# BackEMF.net
KiCad netlist of a schematic drawn in Altium Designer
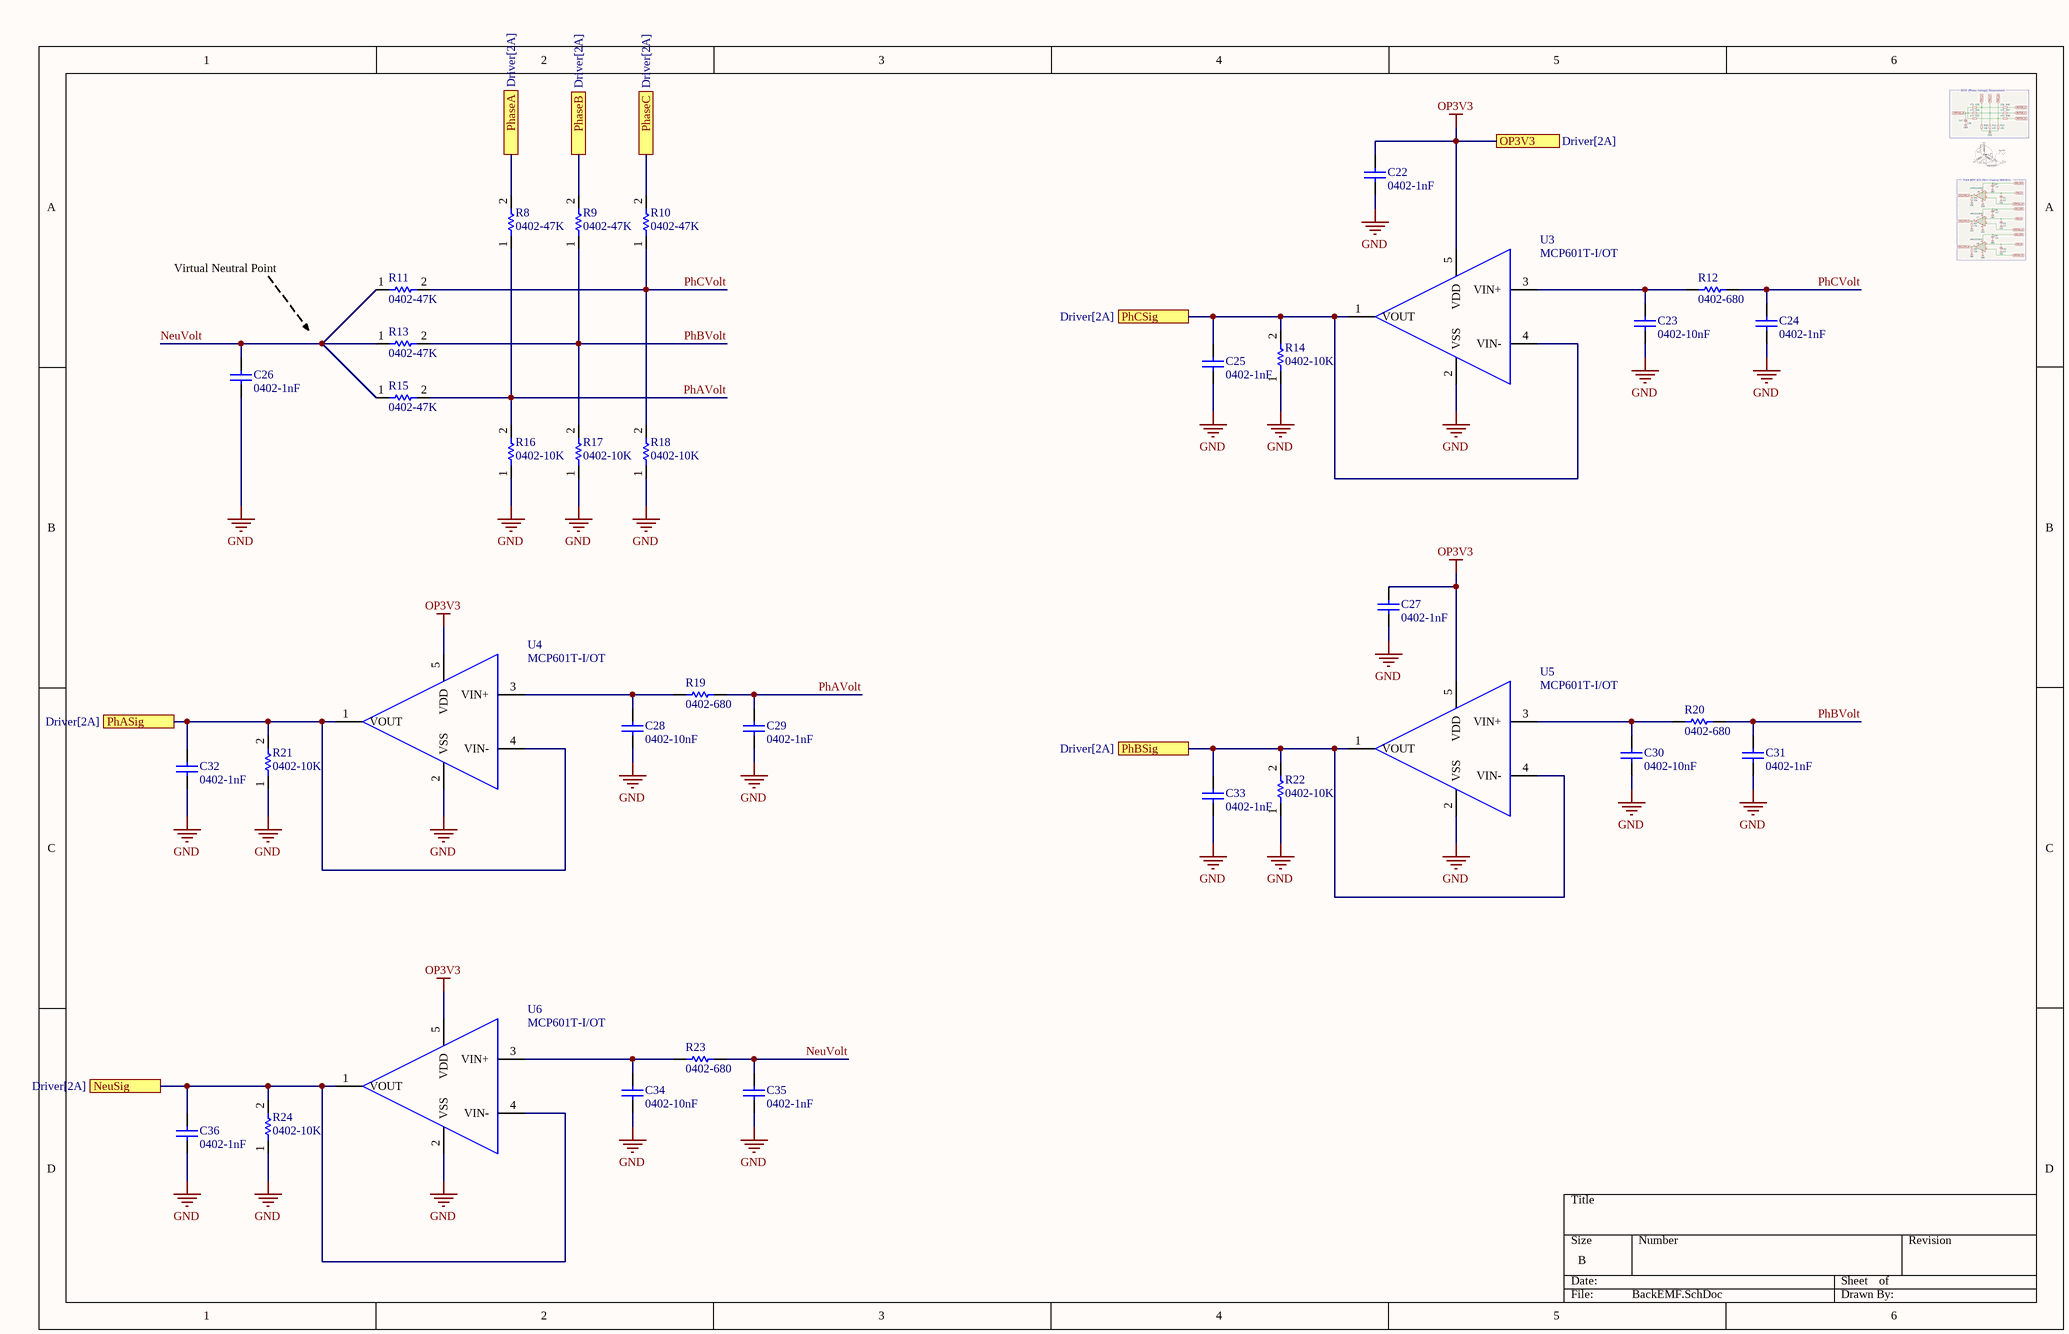
[diagram p0: BackEMF.SchDoc]

(export (version "E")
  (design (tool "Eeschema 10.0.6"))
  (components
    (comp (ref "C22")
      (value "0402-1nF")
      (footprint "CAPC0402(1005)60_N")
      (description "Capacitor 1nF 0402")
      (fields (field (name "TOLERANCE") "20%"))
      (libsource (lib "") (part "0402_1"))
    )
    (comp (ref "C23")
      (value "0402-10nF")
      (footprint "CAPC0402(1005)60_N")
      (description "Capacitor 10nF 0402")
      (fields (field (name "TOLERANCE") "20%"))
      (libsource (lib "") (part "0402_1"))
    )
    (comp (ref "C24")
      (value "0402-1nF")
      (footprint "CAPC0402(1005)60_N")
      (description "Capacitor 1nF 0402")
      (fields (field (name "TOLERANCE") "20%"))
      (libsource (lib "") (part "0402_1"))
    )
    (comp (ref "C25")
      (value "0402-1nF")
      (footprint "CAPC0402(1005)60_N")
      (description "Capacitor 1nF 0402")
      (fields (field (name "TOLERANCE") "20%"))
      (libsource (lib "") (part "0402_1"))
    )
    (comp (ref "C26")
      (value "0402-1nF")
      (footprint "CAPC0402(1005)60_N")
      (description "Capacitor 1nF 0402")
      (fields (field (name "TOLERANCE") "20%"))
      (libsource (lib "") (part "0402_1"))
    )
    (comp (ref "C27")
      (value "0402-1nF")
      (footprint "CAPC0402(1005)60_N")
      (description "Capacitor 1nF 0402")
      (fields (field (name "TOLERANCE") "20%"))
      (libsource (lib "") (part "0402_1"))
    )
    (comp (ref "C28")
      (value "0402-10nF")
      (footprint "CAPC0402(1005)60_N")
      (description "Capacitor 10nF 0402")
      (fields (field (name "TOLERANCE") "20%"))
      (libsource (lib "") (part "0402_1"))
    )
    (comp (ref "C29")
      (value "0402-1nF")
      (footprint "CAPC0402(1005)60_N")
      (description "Capacitor 1nF 0402")
      (fields (field (name "TOLERANCE") "20%"))
      (libsource (lib "") (part "0402_1"))
    )
    (comp (ref "C30")
      (value "0402-10nF")
      (footprint "CAPC0402(1005)60_N")
      (description "Capacitor 10nF 0402")
      (fields (field (name "TOLERANCE") "20%"))
      (libsource (lib "") (part "0402_1"))
    )
    (comp (ref "C31")
      (value "0402-1nF")
      (footprint "CAPC0402(1005)60_N")
      (description "Capacitor 1nF 0402")
      (fields (field (name "TOLERANCE") "20%"))
      (libsource (lib "") (part "0402_1"))
    )
    (comp (ref "C32")
      (value "0402-1nF")
      (footprint "CAPC0402(1005)60_N")
      (description "Capacitor 1nF 0402")
      (fields (field (name "TOLERANCE") "20%"))
      (libsource (lib "") (part "0402_1"))
    )
    (comp (ref "C33")
      (value "0402-1nF")
      (footprint "CAPC0402(1005)60_N")
      (description "Capacitor 1nF 0402")
      (fields (field (name "TOLERANCE") "20%"))
      (libsource (lib "") (part "0402_1"))
    )
    (comp (ref "C34")
      (value "0402-10nF")
      (footprint "CAPC0402(1005)60_N")
      (description "Capacitor 10nF 0402")
      (fields (field (name "TOLERANCE") "20%"))
      (libsource (lib "") (part "0402_1"))
    )
    (comp (ref "C35")
      (value "0402-1nF")
      (footprint "CAPC0402(1005)60_N")
      (description "Capacitor 1nF 0402")
      (fields (field (name "TOLERANCE") "20%"))
      (libsource (lib "") (part "0402_1"))
    )
    (comp (ref "C36")
      (value "0402-1nF")
      (footprint "CAPC0402(1005)60_N")
      (description "Capacitor 1nF 0402")
      (fields (field (name "TOLERANCE") "20%"))
      (libsource (lib "") (part "0402_1"))
    )
    (comp (ref "R8")
      (value "0402-47K")
      (footprint "R-0402-10K")
      (description "RES 0402 47K")
      (libsource (lib "Tin Tran") (part "0402"))
    )
    (comp (ref "R9")
      (value "0402-47K")
      (footprint "R-0402-10K")
      (description "RES 0402 47K")
      (libsource (lib "Tin Tran") (part "0402"))
    )
    (comp (ref "R10")
      (value "0402-47K")
      (footprint "R-0402-10K")
      (description "RES 0402 47K")
      (libsource (lib "Tin Tran") (part "0402"))
    )
    (comp (ref "R11")
      (value "0402-47K")
      (footprint "R-0402-10K")
      (description "RES 0402 47K")
      (libsource (lib "Tin Tran") (part "0402"))
    )
    (comp (ref "R12")
      (value "0402-680")
      (footprint "R-0402-1K")
      (description "0402Resistor 680Ohm")
      (libsource (lib "") (part "0402_2"))
    )
    (comp (ref "R13")
      (value "0402-47K")
      (footprint "R-0402-10K")
      (description "RES 0402 47K")
      (libsource (lib "Tin Tran") (part "0402"))
    )
    (comp (ref "R14")
      (value "0402-10K")
      (footprint "R-0402-10K")
      (description "RES 0402 10K")
      (libsource (lib "Tin Tran") (part "0402"))
    )
    (comp (ref "R15")
      (value "0402-47K")
      (footprint "R-0402-10K")
      (description "RES 0402 47K")
      (libsource (lib "Tin Tran") (part "0402"))
    )
    (comp (ref "R16")
      (value "0402-10K")
      (footprint "R-0402-10K")
      (description "RES 0402 10K")
      (libsource (lib "Tin Tran") (part "0402"))
    )
    (comp (ref "R17")
      (value "0402-10K")
      (footprint "R-0402-10K")
      (description "RES 0402 10K")
      (libsource (lib "Tin Tran") (part "0402"))
    )
    (comp (ref "R18")
      (value "0402-10K")
      (footprint "R-0402-10K")
      (description "RES 0402 10K")
      (libsource (lib "Tin Tran") (part "0402"))
    )
    (comp (ref "R19")
      (value "0402-680")
      (footprint "R-0402-1K")
      (description "0402Resistor 680Ohm")
      (libsource (lib "") (part "0402_2"))
    )
    (comp (ref "R20")
      (value "0402-680")
      (footprint "R-0402-1K")
      (description "0402Resistor 680Ohm")
      (libsource (lib "") (part "0402_2"))
    )
    (comp (ref "R21")
      (value "0402-10K")
      (footprint "R-0402-10K")
      (description "RES 0402 10K")
      (libsource (lib "Tin Tran") (part "0402"))
    )
    (comp (ref "R22")
      (value "0402-10K")
      (footprint "R-0402-10K")
      (description "RES 0402 10K")
      (libsource (lib "Tin Tran") (part "0402"))
    )
    (comp (ref "R23")
      (value "0402-680")
      (footprint "R-0402-1K")
      (description "0402Resistor 680Ohm")
      (libsource (lib "") (part "0402_2"))
    )
    (comp (ref "R24")
      (value "0402-10K")
      (footprint "R-0402-10K")
      (description "RES 0402 10K")
      (libsource (lib "Tin Tran") (part "0402"))
    )
    (comp (ref "U3")
      (value "MCP601T-I/OT")
      (footprint "SOT95P280X145-5N")
      (description "General Purpose Amplifier 1 Circuit Rail-to-Rail SOT-23-5")
      (fields (field (name "MF") "Microchip"))
      (libsource (lib "Tin Tran") (part "MCP601"))
    )
    (comp (ref "U4")
      (value "MCP601T-I/OT")
      (footprint "SOT95P280X145-5N")
      (description "General Purpose Amplifier 1 Circuit Rail-to-Rail SOT-23-5")
      (fields (field (name "MF") "Microchip"))
      (libsource (lib "Tin Tran") (part "MCP601"))
    )
    (comp (ref "U5")
      (value "MCP601T-I/OT")
      (footprint "SOT95P280X145-5N")
      (description "General Purpose Amplifier 1 Circuit Rail-to-Rail SOT-23-5")
      (fields (field (name "MF") "Microchip"))
      (libsource (lib "Tin Tran") (part "MCP601"))
    )
    (comp (ref "U6")
      (value "MCP601T-I/OT")
      (footprint "SOT95P280X145-5N")
      (description "General Purpose Amplifier 1 Circuit Rail-to-Rail SOT-23-5")
      (fields (field (name "MF") "Microchip"))
      (libsource (lib "Tin Tran") (part "MCP601"))
    )
  )
  (nets
    (net (code "1") (name "/NeuSig") (class "Default")
      (node (ref "C36") (pin "2") (pinfunction "2_2") (pintype "passive"))
      (node (ref "R24") (pin "2") (pinfunction "2_2") (pintype "passive"))
      (node (ref "U6") (pin "1") (pinfunction "VOUT_1") (pintype "passive"))
      (node (ref "U6") (pin "4") (pinfunction "VIN-_4") (pintype "passive"))
    )
    (net (code "2") (name "/NeuVolt") (class "Default")
      (node (ref "C26") (pin "2") (pinfunction "2_2") (pintype "passive"))
      (node (ref "C35") (pin "2") (pinfunction "2_2") (pintype "passive"))
      (node (ref "R11") (pin "1") (pinfunction "1_1") (pintype "passive"))
      (node (ref "R13") (pin "1") (pinfunction "1_1") (pintype "passive"))
      (node (ref "R15") (pin "1") (pinfunction "1_1") (pintype "passive"))
      (node (ref "R23") (pin "2") (pinfunction "2_2") (pintype "passive"))
    )
    (net (code "3") (name "/PhASig") (class "Default")
      (node (ref "C32") (pin "2") (pinfunction "2_2") (pintype "passive"))
      (node (ref "R21") (pin "2") (pinfunction "2_2") (pintype "passive"))
      (node (ref "U4") (pin "1") (pinfunction "VOUT_1") (pintype "passive"))
      (node (ref "U4") (pin "4") (pinfunction "VIN-_4") (pintype "passive"))
    )
    (net (code "4") (name "/PhAVolt") (class "Default")
      (node (ref "C29") (pin "2") (pinfunction "2_2") (pintype "passive"))
      (node (ref "R15") (pin "2") (pinfunction "2_2") (pintype "passive"))
      (node (ref "R16") (pin "2") (pinfunction "2_2") (pintype "passive"))
      (node (ref "R19") (pin "2") (pinfunction "2_2") (pintype "passive"))
      (node (ref "R8") (pin "1") (pinfunction "1_1") (pintype "passive"))
    )
    (net (code "5") (name "/PhBSig") (class "Default")
      (node (ref "C33") (pin "2") (pinfunction "2_2") (pintype "passive"))
      (node (ref "R22") (pin "2") (pinfunction "2_2") (pintype "passive"))
      (node (ref "U5") (pin "1") (pinfunction "VOUT_1") (pintype "passive"))
      (node (ref "U5") (pin "4") (pinfunction "VIN-_4") (pintype "passive"))
    )
    (net (code "6") (name "/PhBVolt") (class "Default")
      (node (ref "C31") (pin "2") (pinfunction "2_2") (pintype "passive"))
      (node (ref "R13") (pin "2") (pinfunction "2_2") (pintype "passive"))
      (node (ref "R17") (pin "2") (pinfunction "2_2") (pintype "passive"))
      (node (ref "R20") (pin "2") (pinfunction "2_2") (pintype "passive"))
      (node (ref "R9") (pin "1") (pinfunction "1_1") (pintype "passive"))
    )
    (net (code "7") (name "/PhCSig") (class "Default")
      (node (ref "C25") (pin "2") (pinfunction "2_2") (pintype "passive"))
      (node (ref "R14") (pin "2") (pinfunction "2_2") (pintype "passive"))
      (node (ref "U3") (pin "1") (pinfunction "VOUT_1") (pintype "passive"))
      (node (ref "U3") (pin "4") (pinfunction "VIN-_4") (pintype "passive"))
    )
    (net (code "8") (name "/PhCVolt") (class "Default")
      (node (ref "C24") (pin "2") (pinfunction "2_2") (pintype "passive"))
      (node (ref "R10") (pin "1") (pinfunction "1_1") (pintype "passive"))
      (node (ref "R11") (pin "2") (pinfunction "2_2") (pintype "passive"))
      (node (ref "R12") (pin "2") (pinfunction "2_2") (pintype "passive"))
      (node (ref "R18") (pin "2") (pinfunction "2_2") (pintype "passive"))
    )
    (net (code "9") (name "/PhaseA") (class "Default")
      (node (ref "R8") (pin "2") (pinfunction "2_2") (pintype "passive"))
    )
    (net (code "10") (name "/PhaseB") (class "Default")
      (node (ref "R9") (pin "2") (pinfunction "2_2") (pintype "passive"))
    )
    (net (code "11") (name "/PhaseC") (class "Default")
      (node (ref "R10") (pin "2") (pinfunction "2_2") (pintype "passive"))
    )
    (net (code "12") (name "GND") (class "Default")
      (node (ref "C22") (pin "1") (pinfunction "1_1") (pintype "passive"))
      (node (ref "C23") (pin "1") (pinfunction "1_1") (pintype "passive"))
      (node (ref "C24") (pin "1") (pinfunction "1_1") (pintype "passive"))
      (node (ref "C25") (pin "1") (pinfunction "1_1") (pintype "passive"))
      (node (ref "C26") (pin "1") (pinfunction "1_1") (pintype "passive"))
      (node (ref "C27") (pin "1") (pinfunction "1_1") (pintype "passive"))
      (node (ref "C28") (pin "1") (pinfunction "1_1") (pintype "passive"))
      (node (ref "C29") (pin "1") (pinfunction "1_1") (pintype "passive"))
      (node (ref "C30") (pin "1") (pinfunction "1_1") (pintype "passive"))
      (node (ref "C31") (pin "1") (pinfunction "1_1") (pintype "passive"))
      (node (ref "C32") (pin "1") (pinfunction "1_1") (pintype "passive"))
      (node (ref "C33") (pin "1") (pinfunction "1_1") (pintype "passive"))
      (node (ref "C34") (pin "1") (pinfunction "1_1") (pintype "passive"))
      (node (ref "C35") (pin "1") (pinfunction "1_1") (pintype "passive"))
      (node (ref "C36") (pin "1") (pinfunction "1_1") (pintype "passive"))
      (node (ref "R14") (pin "1") (pinfunction "1_1") (pintype "passive"))
      (node (ref "R16") (pin "1") (pinfunction "1_1") (pintype "passive"))
      (node (ref "R17") (pin "1") (pinfunction "1_1") (pintype "passive"))
      (node (ref "R18") (pin "1") (pinfunction "1_1") (pintype "passive"))
      (node (ref "R21") (pin "1") (pinfunction "1_1") (pintype "passive"))
      (node (ref "R22") (pin "1") (pinfunction "1_1") (pintype "passive"))
      (node (ref "R24") (pin "1") (pinfunction "1_1") (pintype "passive"))
      (node (ref "U3") (pin "2") (pinfunction "VSS_2") (pintype "passive"))
      (node (ref "U4") (pin "2") (pinfunction "VSS_2") (pintype "passive"))
      (node (ref "U5") (pin "2") (pinfunction "VSS_2") (pintype "passive"))
      (node (ref "U6") (pin "2") (pinfunction "VSS_2") (pintype "passive"))
    )
    (net (code "13") (name "Net-(U3-VIN+)") (class "Default")
      (node (ref "C23") (pin "2") (pinfunction "2_2") (pintype "passive"))
      (node (ref "R12") (pin "1") (pinfunction "1_1") (pintype "passive"))
      (node (ref "U3") (pin "3") (pinfunction "VIN+_3") (pintype "passive"))
    )
    (net (code "14") (name "Net-(U4-VIN+)") (class "Default")
      (node (ref "C28") (pin "2") (pinfunction "2_2") (pintype "passive"))
      (node (ref "R19") (pin "1") (pinfunction "1_1") (pintype "passive"))
      (node (ref "U4") (pin "3") (pinfunction "VIN+_3") (pintype "passive"))
    )
    (net (code "15") (name "Net-(U5-VIN+)") (class "Default")
      (node (ref "C30") (pin "2") (pinfunction "2_2") (pintype "passive"))
      (node (ref "R20") (pin "1") (pinfunction "1_1") (pintype "passive"))
      (node (ref "U5") (pin "3") (pinfunction "VIN+_3") (pintype "passive"))
    )
    (net (code "16") (name "Net-(U6-VIN+)") (class "Default")
      (node (ref "C34") (pin "2") (pinfunction "2_2") (pintype "passive"))
      (node (ref "R23") (pin "1") (pinfunction "1_1") (pintype "passive"))
      (node (ref "U6") (pin "3") (pinfunction "VIN+_3") (pintype "passive"))
    )
    (net (code "17") (name "OP3V3") (class "Default")
      (node (ref "C22") (pin "2") (pinfunction "2_2") (pintype "passive"))
      (node (ref "C27") (pin "2") (pinfunction "2_2") (pintype "passive"))
      (node (ref "U3") (pin "5") (pinfunction "VDD_5") (pintype "passive"))
      (node (ref "U4") (pin "5") (pinfunction "VDD_5") (pintype "passive"))
      (node (ref "U5") (pin "5") (pinfunction "VDD_5") (pintype "passive"))
      (node (ref "U6") (pin "5") (pinfunction "VDD_5") (pintype "passive"))
    )
  )
)
